# Arduino_Board.net
KiCad netlist of a schematic drawn in EAGLE
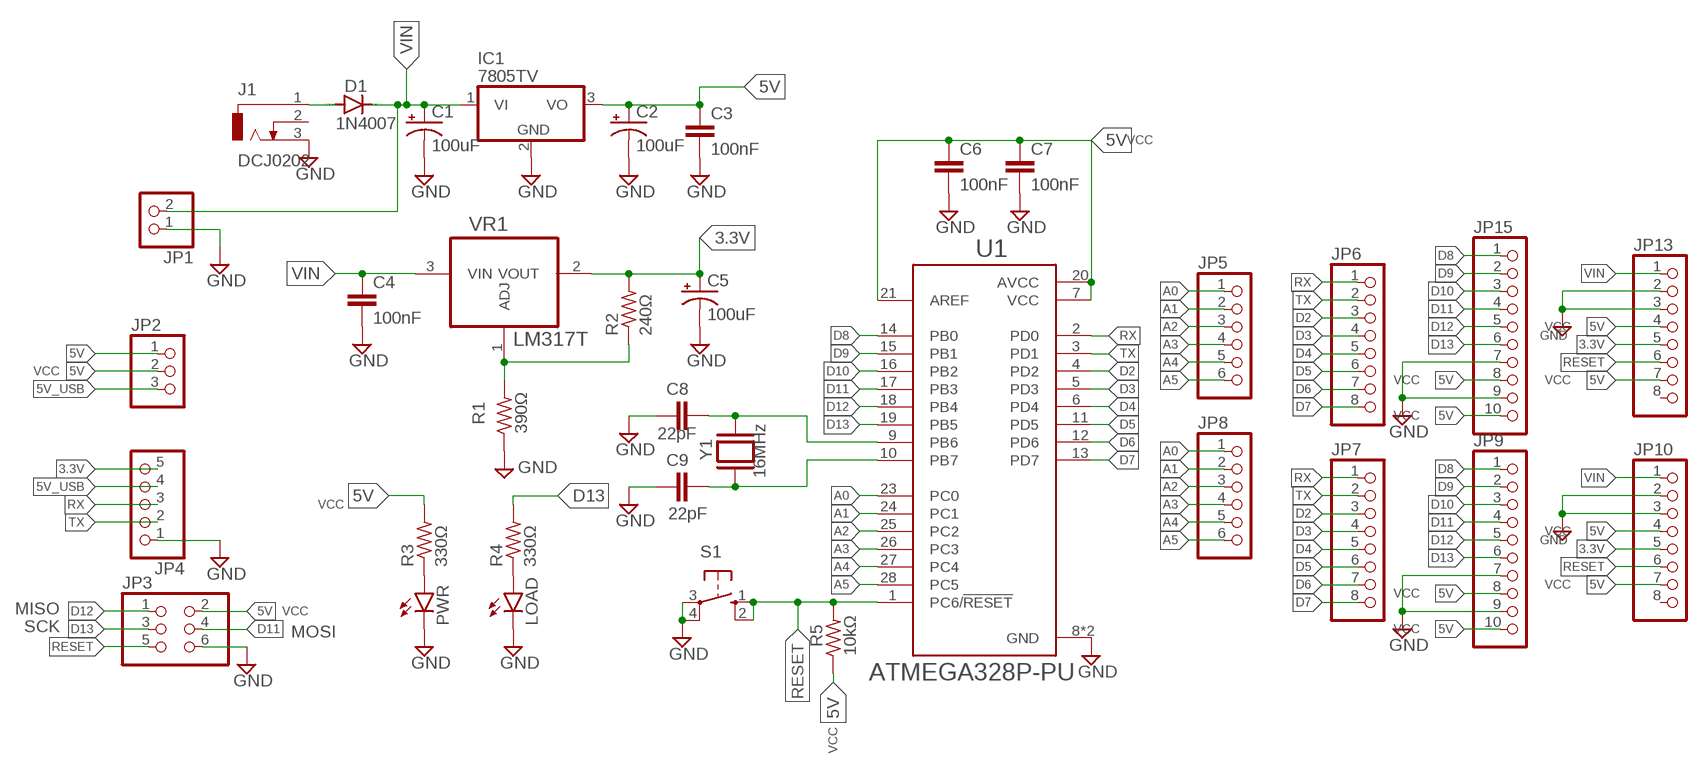
[diagram p0: schematic, sheet 1]

(export (version "E")
  (design (tool "Eeschema 10.0.6"))
  (components
    (comp (ref "C1")
      (value "100uF")
      (footprint "eagle-import:E2,5-6")
      (libsource (lib "eagle-import") (part "CPOL-USE2.5-6"))
    )
    (comp (ref "C2")
      (value "100uF")
      (footprint "eagle-import:E2,5-6")
      (libsource (lib "eagle-import") (part "CPOL-USE2.5-6"))
    )
    (comp (ref "C3")
      (value "100nF")
      (footprint "eagle-import:C025-025X050")
      (libsource (lib "eagle-import") (part "C-EU025-025X050"))
    )
    (comp (ref "C4")
      (value "100nF")
      (footprint "eagle-import:C025-025X050")
      (libsource (lib "eagle-import") (part "C-EU025-025X050"))
    )
    (comp (ref "C5")
      (value "100uF")
      (footprint "eagle-import:E2,5-6")
      (libsource (lib "eagle-import") (part "CPOL-USE2.5-6"))
    )
    (comp (ref "C6")
      (value "100nF")
      (footprint "eagle-import:C025-025X050")
      (libsource (lib "eagle-import") (part "C-EU025-025X050"))
    )
    (comp (ref "C7")
      (value "100nF")
      (footprint "eagle-import:C025-025X050")
      (libsource (lib "eagle-import") (part "C-EU025-025X050"))
    )
    (comp (ref "C8")
      (value "22pF")
      (footprint "eagle-import:C025-025X050")
      (libsource (lib "eagle-import") (part "C-EU025-025X050"))
    )
    (comp (ref "C9")
      (value "22pF")
      (footprint "eagle-import:C025-025X050")
      (libsource (lib "eagle-import") (part "C-EU025-025X050"))
    )
    (comp (ref "D1")
      (value "1N4007")
      (footprint "eagle-import:DO41-10")
      (libsource (lib "eagle-import") (part "1N4007"))
    )
    (comp (ref "IC1")
      (value "7805TV")
      (footprint "eagle-import:TO220V")
      (libsource (lib "eagle-import") (part "78TV05"))
    )
    (comp (ref "J1")
      (value "DCJ0202")
      (footprint "eagle-import:DCJ0202")
      (libsource (lib "eagle-import") (part "DCJ0202"))
    )
    (comp (ref "JP1")
      (value "PINHD-1X2")
      (footprint "eagle-import:1X02")
      (libsource (lib "eagle-import") (part "PINHD-1X2"))
    )
    (comp (ref "JP2")
      (value "PINHD-1X3")
      (footprint "eagle-import:1X03")
      (libsource (lib "eagle-import") (part "PINHD-1X3"))
    )
    (comp (ref "JP3")
      (value "PINHD-2X3")
      (footprint "eagle-import:2X03")
      (libsource (lib "eagle-import") (part "PINHD-2X3"))
    )
    (comp (ref "JP4")
      (value "PINHD-1X5")
      (footprint "eagle-import:1X05")
      (libsource (lib "eagle-import") (part "PINHD-1X5"))
    )
    (comp (ref "JP5")
      (value "PINHD-1X6")
      (footprint "eagle-import:1X06")
      (libsource (lib "eagle-import") (part "PINHD-1X6"))
    )
    (comp (ref "JP6")
      (value "PINHD-1X8")
      (footprint "eagle-import:1X08")
      (libsource (lib "eagle-import") (part "PINHD-1X8"))
    )
    (comp (ref "JP7")
      (value "PINHD-1X8")
      (footprint "eagle-import:1X08")
      (libsource (lib "eagle-import") (part "PINHD-1X8"))
    )
    (comp (ref "JP8")
      (value "PINHD-1X6")
      (footprint "eagle-import:1X06")
      (libsource (lib "eagle-import") (part "PINHD-1X6"))
    )
    (comp (ref "JP9")
      (value "PINHD-1X10")
      (footprint "eagle-import:1X10")
      (libsource (lib "eagle-import") (part "PINHD-1X10"))
    )
    (comp (ref "JP10")
      (value "PINHD-1X8")
      (footprint "eagle-import:1X08")
      (libsource (lib "eagle-import") (part "PINHD-1X8"))
    )
    (comp (ref "JP13")
      (value "PINHD-1X8")
      (footprint "eagle-import:1X08")
      (libsource (lib "eagle-import") (part "PINHD-1X8"))
    )
    (comp (ref "JP15")
      (value "PINHD-1X10")
      (footprint "eagle-import:1X10")
      (libsource (lib "eagle-import") (part "PINHD-1X10"))
    )
    (comp (ref "LOAD")
      (value "LED3MM")
      (footprint "eagle-import:LED3MM")
      (libsource (lib "eagle-import") (part "LED3MM"))
    )
    (comp (ref "PWR")
      (value "LED3MM")
      (footprint "eagle-import:LED3MM")
      (libsource (lib "eagle-import") (part "LED3MM"))
    )
    (comp (ref "R1")
      (value "390Ω")
      (footprint "eagle-import:0204_7")
      (libsource (lib "eagle-import") (part "R-US_0204/7"))
    )
    (comp (ref "R2")
      (value "240Ω")
      (footprint "eagle-import:0204_7")
      (libsource (lib "eagle-import") (part "R-US_0204/7"))
    )
    (comp (ref "R3")
      (value "330Ω")
      (footprint "eagle-import:0204_7")
      (libsource (lib "eagle-import") (part "R-US_0204/7"))
    )
    (comp (ref "R4")
      (value "330Ω")
      (footprint "eagle-import:0204_7")
      (libsource (lib "eagle-import") (part "R-US_0204/7"))
    )
    (comp (ref "R5")
      (value "10kΩ")
      (footprint "eagle-import:0204_7")
      (libsource (lib "eagle-import") (part "R-US_0204/7"))
    )
    (comp (ref "S1")
      (value "10-XX")
      (footprint "eagle-import:B3F-10XX")
      (fields (field (name "MPN") "B3F-1000"))
      (libsource (lib "eagle-import") (part "10-XX"))
    )
    (comp (ref "U1")
      (value "ATMEGA328P-PU")
      (footprint "eagle-import:DIP794W46P254L2967H457Q28B")
      (fields (field (name "MF") "Microchip"))
      (libsource (lib "eagle-import") (part "ATMEGA328P-PU"))
    )
    (comp (ref "VR1")
      (value "LM317T")
      (footprint "eagle-import:TO254P1054X470X1955-3")
      (fields (field (name "MF") "onsemi"))
      (libsource (lib "eagle-import") (part "LM317T"))
    )
    (comp (ref "Y1")
      (value "16MHz")
      (footprint "eagle-import:XTAL_HC49P488W46L1150T500H350")
      (fields (field (name "MF") "Abracon") (field (name "MP") "ABL-16.000MHZ-B2"))
      (libsource (lib "eagle-import") (part "ABL-16.000MHZ-B2"))
    )
  )
  (nets
    (net (code "1") (name "3.3V") (class "Default")
      (node (ref "C5") (pin "+") (pinfunction "+_+") (pintype "passive"))
      (node (ref "JP10") (pin "5") (pinfunction "5_5") (pintype "passive"))
      (node (ref "JP13") (pin "5") (pinfunction "5_5") (pintype "passive"))
      (node (ref "JP4") (pin "5") (pinfunction "5_5") (pintype "passive"))
      (node (ref "R2") (pin "2") (pinfunction "2_2") (pintype "passive"))
      (node (ref "VR1") (pin "2") (pinfunction "VOUT_2") (pintype "output"))
    )
    (net (code "2") (name "5V") (class "Default")
      (node (ref "C2") (pin "+") (pinfunction "+_+") (pintype "passive"))
      (node (ref "C3") (pin "1") (pinfunction "1_1") (pintype "passive"))
      (node (ref "C6") (pin "1") (pinfunction "1_1") (pintype "passive"))
      (node (ref "C7") (pin "1") (pinfunction "1_1") (pintype "passive"))
      (node (ref "IC1") (pin "3") (pinfunction "VO_3") (pintype "passive"))
      (node (ref "JP10") (pin "4") (pinfunction "4_4") (pintype "passive"))
      (node (ref "JP10") (pin "7") (pinfunction "7_7") (pintype "passive"))
      (node (ref "JP13") (pin "4") (pinfunction "4_4") (pintype "passive"))
      (node (ref "JP13") (pin "7") (pinfunction "7_7") (pintype "passive"))
      (node (ref "JP15") (pin "10") (pinfunction "10_10") (pintype "passive"))
      (node (ref "JP15") (pin "8") (pinfunction "8_8") (pintype "passive"))
      (node (ref "JP2") (pin "1") (pinfunction "1_1") (pintype "passive"))
      (node (ref "JP2") (pin "2") (pinfunction "2_2") (pintype "passive"))
      (node (ref "JP3") (pin "2") (pinfunction "2_2") (pintype "passive"))
      (node (ref "JP9") (pin "10") (pinfunction "10_10") (pintype "passive"))
      (node (ref "JP9") (pin "8") (pinfunction "8_8") (pintype "passive"))
      (node (ref "R3") (pin "2") (pinfunction "2_2") (pintype "passive"))
      (node (ref "R5") (pin "1") (pinfunction "1_1") (pintype "passive"))
      (node (ref "U1") (pin "20") (pinfunction "AVCC_20") (pintype "power_in"))
      (node (ref "U1") (pin "21") (pinfunction "AREF_21") (pintype "input"))
      (node (ref "U1") (pin "7") (pinfunction "VCC_7") (pintype "power_in"))
    )
    (net (code "3") (name "5V_USB") (class "Default")
      (node (ref "JP2") (pin "3") (pinfunction "3_3") (pintype "passive"))
      (node (ref "JP4") (pin "4") (pinfunction "4_4") (pintype "passive"))
    )
    (net (code "4") (name "A0") (class "Default")
      (node (ref "JP5") (pin "1") (pinfunction "1_1") (pintype "passive"))
      (node (ref "JP8") (pin "1") (pinfunction "1_1") (pintype "passive"))
      (node (ref "U1") (pin "23") (pinfunction "PC0_23") (pintype "bidirectional"))
    )
    (net (code "5") (name "A1") (class "Default")
      (node (ref "JP5") (pin "2") (pinfunction "2_2") (pintype "passive"))
      (node (ref "JP8") (pin "2") (pinfunction "2_2") (pintype "passive"))
      (node (ref "U1") (pin "24") (pinfunction "PC1_24") (pintype "bidirectional"))
    )
    (net (code "6") (name "A2") (class "Default")
      (node (ref "JP5") (pin "3") (pinfunction "3_3") (pintype "passive"))
      (node (ref "JP8") (pin "3") (pinfunction "3_3") (pintype "passive"))
      (node (ref "U1") (pin "25") (pinfunction "PC2_25") (pintype "bidirectional"))
    )
    (net (code "7") (name "A3") (class "Default")
      (node (ref "JP5") (pin "4") (pinfunction "4_4") (pintype "passive"))
      (node (ref "JP8") (pin "4") (pinfunction "4_4") (pintype "passive"))
      (node (ref "U1") (pin "26") (pinfunction "PC3_26") (pintype "bidirectional"))
    )
    (net (code "8") (name "A4") (class "Default")
      (node (ref "JP5") (pin "5") (pinfunction "5_5") (pintype "passive"))
      (node (ref "JP8") (pin "5") (pinfunction "5_5") (pintype "passive"))
      (node (ref "U1") (pin "27") (pinfunction "PC4_27") (pintype "bidirectional"))
    )
    (net (code "9") (name "A5") (class "Default")
      (node (ref "JP5") (pin "6") (pinfunction "6_6") (pintype "passive"))
      (node (ref "JP8") (pin "6") (pinfunction "6_6") (pintype "passive"))
      (node (ref "U1") (pin "28") (pinfunction "PC5_28") (pintype "bidirectional"))
    )
    (net (code "10") (name "D2") (class "Default")
      (node (ref "JP6") (pin "3") (pinfunction "3_3") (pintype "passive"))
      (node (ref "JP7") (pin "3") (pinfunction "3_3") (pintype "passive"))
      (node (ref "U1") (pin "4") (pinfunction "PD2_4") (pintype "bidirectional"))
    )
    (net (code "11") (name "D3") (class "Default")
      (node (ref "JP6") (pin "4") (pinfunction "4_4") (pintype "passive"))
      (node (ref "JP7") (pin "4") (pinfunction "4_4") (pintype "passive"))
      (node (ref "U1") (pin "5") (pinfunction "PD3_5") (pintype "bidirectional"))
    )
    (net (code "12") (name "D4") (class "Default")
      (node (ref "JP6") (pin "5") (pinfunction "5_5") (pintype "passive"))
      (node (ref "JP7") (pin "5") (pinfunction "5_5") (pintype "passive"))
      (node (ref "U1") (pin "6") (pinfunction "PD4_6") (pintype "bidirectional"))
    )
    (net (code "13") (name "D5") (class "Default")
      (node (ref "JP6") (pin "6") (pinfunction "6_6") (pintype "passive"))
      (node (ref "JP7") (pin "6") (pinfunction "6_6") (pintype "passive"))
      (node (ref "U1") (pin "11") (pinfunction "PD5_11") (pintype "bidirectional"))
    )
    (net (code "14") (name "D6") (class "Default")
      (node (ref "JP6") (pin "7") (pinfunction "7_7") (pintype "passive"))
      (node (ref "JP7") (pin "7") (pinfunction "7_7") (pintype "passive"))
      (node (ref "U1") (pin "12") (pinfunction "PD6_12") (pintype "bidirectional"))
    )
    (net (code "15") (name "D7") (class "Default")
      (node (ref "JP6") (pin "8") (pinfunction "8_8") (pintype "passive"))
      (node (ref "JP7") (pin "8") (pinfunction "8_8") (pintype "passive"))
      (node (ref "U1") (pin "13") (pinfunction "PD7_13") (pintype "bidirectional"))
    )
    (net (code "16") (name "D8") (class "Default")
      (node (ref "JP15") (pin "1") (pinfunction "1_1") (pintype "passive"))
      (node (ref "JP9") (pin "1") (pinfunction "1_1") (pintype "passive"))
      (node (ref "U1") (pin "14") (pinfunction "PB0_14") (pintype "bidirectional"))
    )
    (net (code "17") (name "D9") (class "Default")
      (node (ref "JP15") (pin "2") (pinfunction "2_2") (pintype "passive"))
      (node (ref "JP9") (pin "2") (pinfunction "2_2") (pintype "passive"))
      (node (ref "U1") (pin "15") (pinfunction "PB1_15") (pintype "bidirectional"))
    )
    (net (code "18") (name "D10") (class "Default")
      (node (ref "JP15") (pin "3") (pinfunction "3_3") (pintype "passive"))
      (node (ref "JP9") (pin "3") (pinfunction "3_3") (pintype "passive"))
      (node (ref "U1") (pin "16") (pinfunction "PB2_16") (pintype "bidirectional"))
    )
    (net (code "19") (name "D11") (class "Default")
      (node (ref "JP15") (pin "4") (pinfunction "4_4") (pintype "passive"))
      (node (ref "JP3") (pin "4") (pinfunction "4_4") (pintype "passive"))
      (node (ref "JP9") (pin "4") (pinfunction "4_4") (pintype "passive"))
      (node (ref "U1") (pin "17") (pinfunction "PB3_17") (pintype "bidirectional"))
    )
    (net (code "20") (name "D12") (class "Default")
      (node (ref "JP15") (pin "5") (pinfunction "5_5") (pintype "passive"))
      (node (ref "JP3") (pin "1") (pinfunction "1_1") (pintype "passive"))
      (node (ref "JP9") (pin "5") (pinfunction "5_5") (pintype "passive"))
      (node (ref "U1") (pin "18") (pinfunction "PB4_18") (pintype "bidirectional"))
    )
    (net (code "21") (name "D13") (class "Default")
      (node (ref "JP15") (pin "6") (pinfunction "6_6") (pintype "passive"))
      (node (ref "JP3") (pin "3") (pinfunction "3_3") (pintype "passive"))
      (node (ref "JP9") (pin "6") (pinfunction "6_6") (pintype "passive"))
      (node (ref "R4") (pin "2") (pinfunction "2_2") (pintype "passive"))
      (node (ref "U1") (pin "19") (pinfunction "PB5_19") (pintype "bidirectional"))
    )
    (net (code "22") (name "GND") (class "Default")
      (node (ref "C1") (pin "-") (pinfunction "-_-") (pintype "passive"))
      (node (ref "C2") (pin "-") (pinfunction "-_-") (pintype "passive"))
      (node (ref "C3") (pin "2") (pinfunction "2_2") (pintype "passive"))
      (node (ref "C4") (pin "2") (pinfunction "2_2") (pintype "passive"))
      (node (ref "C5") (pin "-") (pinfunction "-_-") (pintype "passive"))
      (node (ref "C6") (pin "2") (pinfunction "2_2") (pintype "passive"))
      (node (ref "C7") (pin "2") (pinfunction "2_2") (pintype "passive"))
      (node (ref "C8") (pin "1") (pinfunction "1_1") (pintype "passive"))
      (node (ref "C9") (pin "1") (pinfunction "1_1") (pintype "passive"))
      (node (ref "IC1") (pin "2") (pinfunction "GND_2") (pintype "passive"))
      (node (ref "J1") (pin "3") (pinfunction "3_3") (pintype "passive"))
      (node (ref "JP1") (pin "1") (pinfunction "1_1") (pintype "passive"))
      (node (ref "JP10") (pin "2") (pinfunction "2_2") (pintype "passive"))
      (node (ref "JP10") (pin "3") (pinfunction "3_3") (pintype "passive"))
      (node (ref "JP13") (pin "2") (pinfunction "2_2") (pintype "passive"))
      (node (ref "JP13") (pin "3") (pinfunction "3_3") (pintype "passive"))
      (node (ref "JP15") (pin "7") (pinfunction "7_7") (pintype "passive"))
      (node (ref "JP15") (pin "9") (pinfunction "9_9") (pintype "passive"))
      (node (ref "JP3") (pin "6") (pinfunction "6_6") (pintype "passive"))
      (node (ref "JP4") (pin "1") (pinfunction "1_1") (pintype "passive"))
      (node (ref "JP9") (pin "7") (pinfunction "7_7") (pintype "passive"))
      (node (ref "JP9") (pin "9") (pinfunction "9_9") (pintype "passive"))
      (node (ref "LOAD") (pin "K") (pinfunction "C_K") (pintype "passive"))
      (node (ref "PWR") (pin "K") (pinfunction "C_K") (pintype "passive"))
      (node (ref "R1") (pin "1") (pinfunction "1_1") (pintype "passive"))
      (node (ref "S1") (pin "3") (pinfunction "P_3") (pintype "passive"))
      (node (ref "S1") (pin "4") (pinfunction "P1_4") (pintype "passive"))
      (node (ref "U1") (pin "22") (pinfunction "GND_22") (pintype "power_in"))
      (node (ref "U1") (pin "8") (pinfunction "GND_8") (pintype "power_in"))
    )
    (net (code "23") (name "Net-(D1-PadA)") (class "Default")
      (node (ref "D1") (pin "A") (pinfunction "A_A") (pintype "passive"))
      (node (ref "J1") (pin "1") (pinfunction "1_1") (pintype "passive"))
    )
    (net (code "24") (name "Net-(LOAD-PadA)") (class "Default")
      (node (ref "LOAD") (pin "A") (pinfunction "A_A") (pintype "passive"))
      (node (ref "R4") (pin "1") (pinfunction "1_1") (pintype "passive"))
    )
    (net (code "25") (name "Net-(PWR-PadA)") (class "Default")
      (node (ref "PWR") (pin "A") (pinfunction "A_A") (pintype "passive"))
      (node (ref "R3") (pin "1") (pinfunction "1_1") (pintype "passive"))
    )
    (net (code "26") (name "Net-(U1-PB6)") (class "Default")
      (node (ref "C8") (pin "2") (pinfunction "2_2") (pintype "passive"))
      (node (ref "U1") (pin "9") (pinfunction "PB6_9") (pintype "bidirectional"))
      (node (ref "Y1") (pin "2") (pinfunction "2_2") (pintype "passive"))
    )
    (net (code "27") (name "Net-(U1-PB7)") (class "Default")
      (node (ref "C9") (pin "2") (pinfunction "2_2") (pintype "passive"))
      (node (ref "U1") (pin "10") (pinfunction "PB7_10") (pintype "bidirectional"))
      (node (ref "Y1") (pin "1") (pinfunction "1_1") (pintype "passive"))
    )
    (net (code "28") (name "Net-(VR1-ADJ)") (class "Default")
      (node (ref "R1") (pin "2") (pinfunction "2_2") (pintype "passive"))
      (node (ref "R2") (pin "1") (pinfunction "1_1") (pintype "passive"))
      (node (ref "VR1") (pin "1") (pinfunction "ADJ_1") (pintype "input"))
    )
    (net (code "29") (name "RESET") (class "Default")
      (node (ref "JP10") (pin "6") (pinfunction "6_6") (pintype "passive"))
      (node (ref "JP13") (pin "6") (pinfunction "6_6") (pintype "passive"))
      (node (ref "JP3") (pin "5") (pinfunction "5_5") (pintype "passive"))
      (node (ref "R5") (pin "2") (pinfunction "2_2") (pintype "passive"))
      (node (ref "S1") (pin "1") (pinfunction "S_1") (pintype "passive"))
      (node (ref "S1") (pin "2") (pinfunction "S1_2") (pintype "passive"))
      (node (ref "U1") (pin "1") (pinfunction "PC6/~{RESET}_1") (pintype "bidirectional"))
    )
    (net (code "30") (name "RX") (class "Default")
      (node (ref "JP4") (pin "3") (pinfunction "3_3") (pintype "passive"))
      (node (ref "JP6") (pin "1") (pinfunction "1_1") (pintype "passive"))
      (node (ref "JP7") (pin "1") (pinfunction "1_1") (pintype "passive"))
      (node (ref "U1") (pin "2") (pinfunction "PD0_2") (pintype "bidirectional"))
    )
    (net (code "31") (name "TX") (class "Default")
      (node (ref "JP4") (pin "2") (pinfunction "2_2") (pintype "passive"))
      (node (ref "JP6") (pin "2") (pinfunction "2_2") (pintype "passive"))
      (node (ref "JP7") (pin "2") (pinfunction "2_2") (pintype "passive"))
      (node (ref "U1") (pin "3") (pinfunction "PD1_3") (pintype "bidirectional"))
    )
    (net (code "32") (name "VIN") (class "Default")
      (node (ref "C1") (pin "+") (pinfunction "+_+") (pintype "passive"))
      (node (ref "C4") (pin "1") (pinfunction "1_1") (pintype "passive"))
      (node (ref "D1") (pin "C") (pinfunction "C_C") (pintype "passive"))
      (node (ref "IC1") (pin "1") (pinfunction "VI_1") (pintype "input"))
      (node (ref "JP1") (pin "2") (pinfunction "2_2") (pintype "passive"))
      (node (ref "JP10") (pin "1") (pinfunction "1_1") (pintype "passive"))
      (node (ref "JP13") (pin "1") (pinfunction "1_1") (pintype "passive"))
      (node (ref "VR1") (pin "3") (pinfunction "VIN_3") (pintype "input"))
    )
    (net (code "33") (name "unconnected-(J1-Pad2)") (class "Default")
      (node (ref "J1") (pin "2") (pinfunction "2_2") (pintype "passive"))
    )
    (net (code "34") (name "unconnected-(JP10-Pad8)") (class "Default")
      (node (ref "JP10") (pin "8") (pinfunction "8_8") (pintype "passive"))
    )
    (net (code "35") (name "unconnected-(JP13-Pad8)") (class "Default")
      (node (ref "JP13") (pin "8") (pinfunction "8_8") (pintype "passive"))
    )
  )
)
